# dc-motor.net
KiCad netlist of a schematic drawn in EAGLE
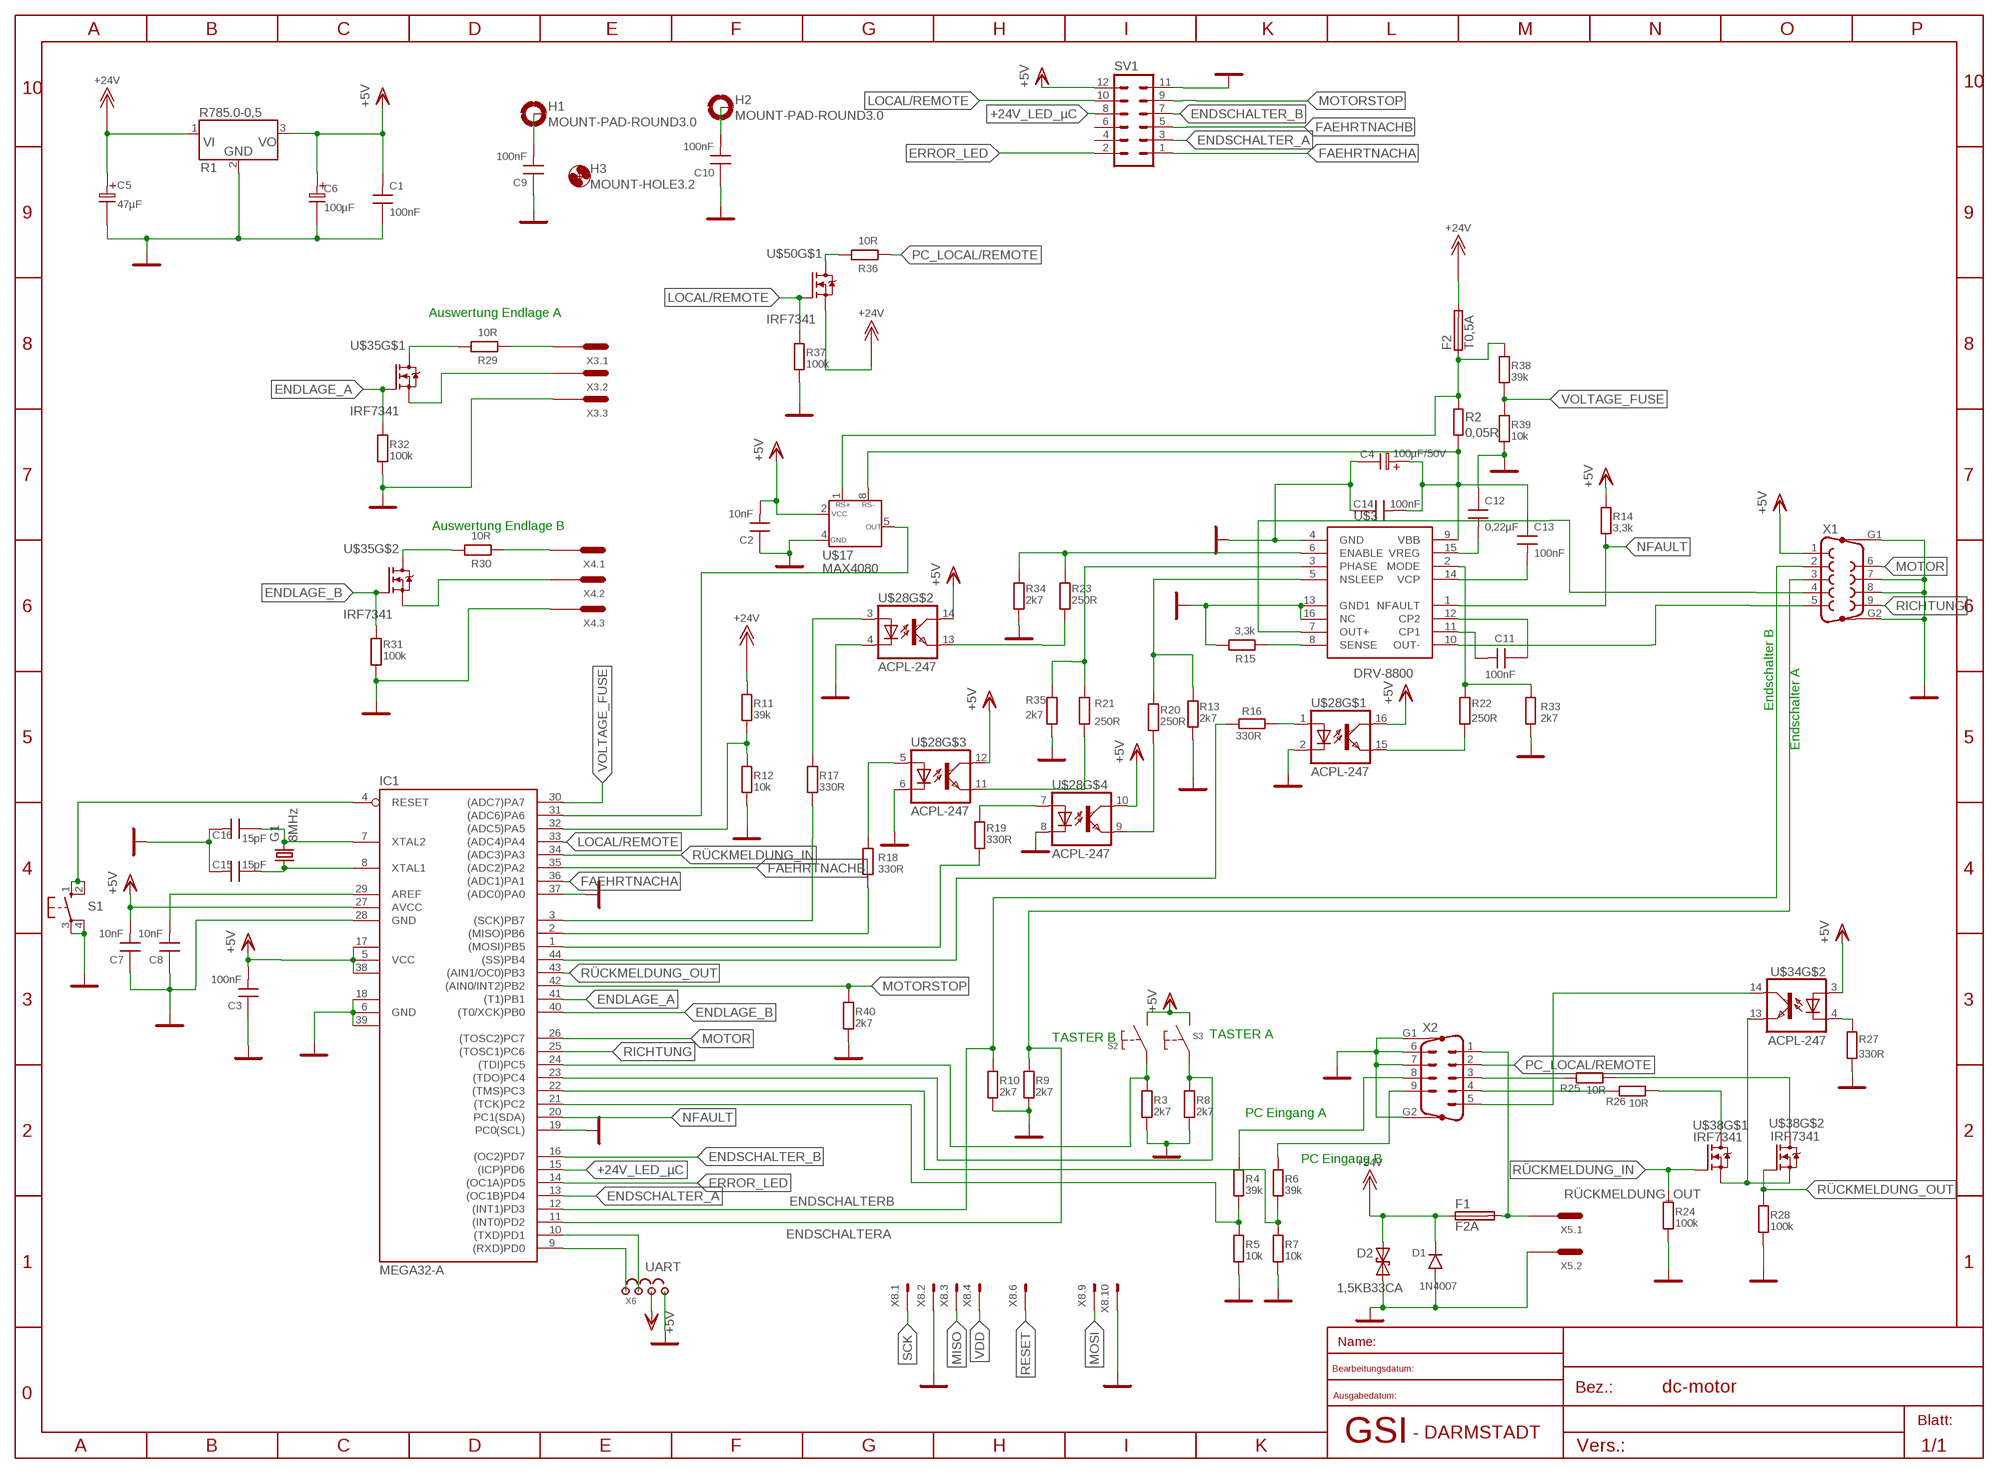
[diagram p0: schematic, sheet 1]

(export (version "E")
  (design (tool "Eeschema 10.0.6"))
  (components
    (comp (ref "C1")
      (value "100nF")
      (footprint "eagle-import:0805")
      (libsource (lib "eagle-import") (part "C-BELAB0805"))
    )
    (comp (ref "C2")
      (value "10nF")
      (footprint "eagle-import:0805")
      (libsource (lib "eagle-import") (part "C-BELAB0805"))
    )
    (comp (ref "C3")
      (value "100nF")
      (footprint "eagle-import:0805")
      (libsource (lib "eagle-import") (part "C-BELAB0805"))
    )
    (comp (ref "C4")
      (value "100µF/50V")
      (footprint "eagle-import:E5-13")
      (libsource (lib "eagle-import") (part "ELK_STEHEND_5_13"))
    )
    (comp (ref "C5")
      (value "47µF")
      (footprint "eagle-import:E5-13")
      (libsource (lib "eagle-import") (part "ELK_STEHEND_5_13"))
    )
    (comp (ref "C6")
      (value "100µF")
      (footprint "eagle-import:E5-13")
      (libsource (lib "eagle-import") (part "ELK_STEHEND_5_13"))
    )
    (comp (ref "C7")
      (value "10nF")
      (footprint "eagle-import:0805")
      (libsource (lib "eagle-import") (part "C-BELAB0805"))
    )
    (comp (ref "C8")
      (value "10nF")
      (footprint "eagle-import:0805")
      (libsource (lib "eagle-import") (part "C-BELAB0805"))
    )
    (comp (ref "C9")
      (value "100nF")
      (footprint "eagle-import:0805")
      (libsource (lib "eagle-import") (part "C-BELAB0805"))
    )
    (comp (ref "C10")
      (value "100nF")
      (footprint "eagle-import:0805")
      (libsource (lib "eagle-import") (part "C-BELAB0805"))
    )
    (comp (ref "C11")
      (value "100nF")
      (footprint "eagle-import:0805")
      (libsource (lib "eagle-import") (part "C-BELAB0805"))
    )
    (comp (ref "C12")
      (value "0,22µF")
      (footprint "eagle-import:0805")
      (libsource (lib "eagle-import") (part "C-BELAB0805"))
    )
    (comp (ref "C13")
      (value "100nF")
      (footprint "eagle-import:0805")
      (libsource (lib "eagle-import") (part "C-BELAB0805"))
    )
    (comp (ref "C14")
      (value "100nF")
      (footprint "eagle-import:0805")
      (libsource (lib "eagle-import") (part "C-BELAB0805"))
    )
    (comp (ref "C15")
      (value "15pF")
      (footprint "eagle-import:0805")
      (libsource (lib "eagle-import") (part "C-BELAB0805"))
    )
    (comp (ref "C16")
      (value "15pF")
      (footprint "eagle-import:0805")
      (libsource (lib "eagle-import") (part "C-BELAB0805"))
    )
    (comp (ref "D1")
      (value "1N4007")
      (footprint "eagle-import:RM10DR1")
      (libsource (lib "eagle-import") (part "1N4007"))
    )
    (comp (ref "D2")
      (value "1,5KB33CA")
      (footprint "eagle-import:CB417-15")
      (libsource (lib "eagle-import") (part "P6KEXXC"))
    )
    (comp (ref "F1")
      (value "F2A")
      (footprint "eagle-import:F457")
      (libsource (lib "eagle-import") (part "F457"))
    )
    (comp (ref "F2")
      (value "T0,5A")
      (footprint "eagle-import:F457")
      (libsource (lib "eagle-import") (part "F457"))
    )
    (comp (ref "G1")
      (value "8MHz")
      (footprint "eagle-import:HC18U-V")
      (libsource (lib "eagle-import") (part "CRYTALHC18U-V"))
    )
    (comp (ref "H1")
      (value "MOUNT-PAD-ROUND3.0")
      (footprint "eagle-import:3,0-PAD")
      (libsource (lib "eagle-import") (part "MOUNT-PAD-ROUND3.0"))
    )
    (comp (ref "H2")
      (value "MOUNT-PAD-ROUND3.0")
      (footprint "eagle-import:3,0-PAD")
      (libsource (lib "eagle-import") (part "MOUNT-PAD-ROUND3.0"))
    )
    (comp (ref "H3")
      (value "MOUNT-HOLE3.2")
      (footprint "eagle-import:3,2")
      (libsource (lib "eagle-import") (part "MOUNT-HOLE3.2"))
    )
    (comp (ref "IC1")
      (value "MEGA32-A")
      (footprint "eagle-import:TQFP44")
      (fields
        (field (name "MPN") "ATMEGA32-16AU")
        (field (name "MPN_1") "ATMEGA32-16AU")
        (field (name "OC_FARNELL") "9171274")
        (field (name "OC_NEWARK") "69K6677")
      )
      (libsource (lib "eagle-import") (part "MEGA32-A"))
    )
    (comp (ref "R1")
      (value "R785.0-0,5")
      (footprint "eagle-import:SIP3")
      (libsource (lib "eagle-import") (part "R-785.0-0.5"))
    )
    (comp (ref "R2")
      (value "0,05R")
      (footprint "eagle-import:SMS-0")
      (libsource (lib "eagle-import") (part "SMS-0"))
    )
    (comp (ref "R3")
      (value "2k7")
      (footprint "eagle-import:0805")
      (libsource (lib "eagle-import") (part "0805"))
    )
    (comp (ref "R4")
      (value "39k")
      (footprint "eagle-import:0805")
      (libsource (lib "eagle-import") (part "0805"))
    )
    (comp (ref "R5")
      (value "10k")
      (footprint "eagle-import:0805")
      (libsource (lib "eagle-import") (part "0805"))
    )
    (comp (ref "R6")
      (value "39k")
      (footprint "eagle-import:0805")
      (libsource (lib "eagle-import") (part "0805"))
    )
    (comp (ref "R7")
      (value "10k")
      (footprint "eagle-import:0805")
      (libsource (lib "eagle-import") (part "0805"))
    )
    (comp (ref "R8")
      (value "2k7")
      (footprint "eagle-import:0805")
      (libsource (lib "eagle-import") (part "0805"))
    )
    (comp (ref "R9")
      (value "2k7")
      (footprint "eagle-import:0805")
      (libsource (lib "eagle-import") (part "0805"))
    )
    (comp (ref "R10")
      (value "2k7")
      (footprint "eagle-import:0805")
      (libsource (lib "eagle-import") (part "0805"))
    )
    (comp (ref "R11")
      (value "39k")
      (footprint "eagle-import:0805")
      (libsource (lib "eagle-import") (part "0805"))
    )
    (comp (ref "R12")
      (value "10k")
      (footprint "eagle-import:0805")
      (libsource (lib "eagle-import") (part "0805"))
    )
    (comp (ref "R13")
      (value "2k7")
      (footprint "eagle-import:0805")
      (libsource (lib "eagle-import") (part "0805"))
    )
    (comp (ref "R14")
      (value "3,3k")
      (footprint "eagle-import:0805")
      (libsource (lib "eagle-import") (part "0805"))
    )
    (comp (ref "R15")
      (value "3,3k")
      (footprint "eagle-import:0805")
      (libsource (lib "eagle-import") (part "0805"))
    )
    (comp (ref "R16")
      (value "330R")
      (footprint "eagle-import:0805")
      (libsource (lib "eagle-import") (part "0805"))
    )
    (comp (ref "R17")
      (value "330R")
      (footprint "eagle-import:0805")
      (libsource (lib "eagle-import") (part "0805"))
    )
    (comp (ref "R18")
      (value "330R")
      (footprint "eagle-import:0805")
      (libsource (lib "eagle-import") (part "0805"))
    )
    (comp (ref "R19")
      (value "330R")
      (footprint "eagle-import:0805")
      (libsource (lib "eagle-import") (part "0805"))
    )
    (comp (ref "R20")
      (value "250R")
      (footprint "eagle-import:0805")
      (libsource (lib "eagle-import") (part "0805"))
    )
    (comp (ref "R21")
      (value "250R")
      (footprint "eagle-import:0805")
      (libsource (lib "eagle-import") (part "0805"))
    )
    (comp (ref "R22")
      (value "250R")
      (footprint "eagle-import:0805")
      (libsource (lib "eagle-import") (part "0805"))
    )
    (comp (ref "R23")
      (value "250R")
      (footprint "eagle-import:0805")
      (libsource (lib "eagle-import") (part "0805"))
    )
    (comp (ref "R24")
      (value "100k")
      (footprint "eagle-import:0805")
      (libsource (lib "eagle-import") (part "0805"))
    )
    (comp (ref "R25")
      (value "10R")
      (footprint "eagle-import:0805")
      (libsource (lib "eagle-import") (part "0805"))
    )
    (comp (ref "R26")
      (value "10R")
      (footprint "eagle-import:0805")
      (libsource (lib "eagle-import") (part "0805"))
    )
    (comp (ref "R27")
      (value "330R")
      (footprint "eagle-import:0805")
      (libsource (lib "eagle-import") (part "0805"))
    )
    (comp (ref "R28")
      (value "100k")
      (footprint "eagle-import:0805")
      (libsource (lib "eagle-import") (part "0805"))
    )
    (comp (ref "R29")
      (value "10R")
      (footprint "eagle-import:0805")
      (libsource (lib "eagle-import") (part "0805"))
    )
    (comp (ref "R30")
      (value "10R")
      (footprint "eagle-import:0805")
      (libsource (lib "eagle-import") (part "0805"))
    )
    (comp (ref "R31")
      (value "100k")
      (footprint "eagle-import:0805")
      (libsource (lib "eagle-import") (part "0805"))
    )
    (comp (ref "R32")
      (value "100k")
      (footprint "eagle-import:0805")
      (libsource (lib "eagle-import") (part "0805"))
    )
    (comp (ref "R33")
      (value "2k7")
      (footprint "eagle-import:0805")
      (libsource (lib "eagle-import") (part "0805"))
    )
    (comp (ref "R34")
      (value "2k7")
      (footprint "eagle-import:0805")
      (libsource (lib "eagle-import") (part "0805"))
    )
    (comp (ref "R35")
      (value "2k7")
      (footprint "eagle-import:0805")
      (libsource (lib "eagle-import") (part "0805"))
    )
    (comp (ref "R36")
      (value "10R")
      (footprint "eagle-import:0805")
      (libsource (lib "eagle-import") (part "0805"))
    )
    (comp (ref "R37")
      (value "100k")
      (footprint "eagle-import:0805")
      (libsource (lib "eagle-import") (part "0805"))
    )
    (comp (ref "R38")
      (value "39k")
      (footprint "eagle-import:0805")
      (libsource (lib "eagle-import") (part "0805"))
    )
    (comp (ref "R39")
      (value "10k")
      (footprint "eagle-import:0805")
      (libsource (lib "eagle-import") (part "0805"))
    )
    (comp (ref "R40")
      (value "2k7")
      (footprint "eagle-import:0805")
      (libsource (lib "eagle-import") (part "0805"))
    )
    (comp (ref "S1")
      (value "10-XX")
      (footprint "eagle-import:B3F-10XX")
      (libsource (lib "eagle-import") (part "10-XX"))
    )
    (comp (ref "S2")
      (value "DRUCKTASTER_ABGW")
      (footprint "eagle-import:1_POL_ABGW")
      (libsource (lib "eagle-import") (part "DRUCKTASTER_ABGW"))
    )
    (comp (ref "S3")
      (value "DRUCKTASTER_ABGW")
      (footprint "eagle-import:1_POL_ABGW")
      (libsource (lib "eagle-import") (part "DRUCKTASTER_ABGW"))
    )
    (comp (ref "SV1")
      (value "MA06-2")
      (footprint "eagle-import:MA06-2")
      (libsource (lib "eagle-import") (part "MA06-2"))
    )
    (comp (ref "U$3")
      (value "DRV-8800")
      (footprint "eagle-import:TSSOP16")
      (libsource (lib "eagle-import") (part "DRV-8800"))
    )
    (comp (ref "U$17")
      (value "MAX4080")
      (footprint "eagle-import:MAX4080")
      (libsource (lib "eagle-import") (part "MAX4080"))
    )
    (comp (ref "U$28")
      (value "ACPL-247")
      (footprint "eagle-import:SOIC16")
      (libsource (lib "eagle-import") (part "ACPL-247"))
    )
    (comp (ref "U$34")
      (value "ACPL-247")
      (footprint "eagle-import:SOIC16")
      (libsource (lib "eagle-import") (part "ACPL-247"))
    )
    (comp (ref "U$35")
      (value "IRF7341")
      (footprint "eagle-import:SO08-IRF")
      (libsource (lib "eagle-import") (part "IRF7341"))
    )
    (comp (ref "U$38")
      (value "IRF7341")
      (footprint "eagle-import:SO08-IRF")
      (libsource (lib "eagle-import") (part "IRF7341"))
    )
    (comp (ref "U$50")
      (value "IRF7341")
      (footprint "eagle-import:SO08-IRF")
      (libsource (lib "eagle-import") (part "IRF7341"))
    )
    (comp (ref "X1")
      (value "F09HP")
      (footprint "eagle-import:F09HP")
      (libsource (lib "eagle-import") (part "F09HP"))
    )
    (comp (ref "X2")
      (value "M09HP")
      (footprint "eagle-import:M09HP")
      (libsource (lib "eagle-import") (part "M09HP"))
    )
    (comp (ref "X3")
      (value "RIA_3POL")
      (footprint "eagle-import:RIA_3POL")
      (libsource (lib "eagle-import") (part "RIA_3POL"))
    )
    (comp (ref "X4")
      (value "RIA_3POL")
      (footprint "eagle-import:RIA_3POL")
      (libsource (lib "eagle-import") (part "RIA_3POL"))
    )
    (comp (ref "X5")
      (value "RIA_2POL")
      (footprint "eagle-import:RIA_2POL")
      (libsource (lib "eagle-import") (part "RIA_2POL"))
    )
    (comp (ref "X6")
      (value "JUMP1-4")
      (footprint "eagle-import:JUMP1-4")
      (libsource (lib "eagle-import") (part "JUMP1-4"))
    )
    (comp (ref "X8")
      (value "PFVERB10")
      (footprint "eagle-import:PFVERB10")
      (libsource (lib "eagle-import") (part "PFVERB10"))
    )
  )
  (nets
    (net (code "1") (name "+24V") (class "Default")
      (node (ref "C5") (pin "+") (pinfunction "+_+") (pintype "passive"))
      (node (ref "D1") (pin "K") (pinfunction "K_K") (pintype "passive"))
      (node (ref "D2") (pin "C") (pinfunction "2_C") (pintype "passive"))
      (node (ref "F1") (pin "1") (pinfunction "1_1") (pintype "passive"))
      (node (ref "F2") (pin "2") (pinfunction "2_2") (pintype "passive"))
      (node (ref "R1") (pin "1") (pinfunction "1_1") (pintype "input"))
      (node (ref "R11") (pin "2") (pinfunction "2_2") (pintype "passive"))
      (node (ref "U$50") (pin "1") (pinfunction "N-S1_1") (pintype "passive"))
    )
    (net (code "2") (name "+24V_LED_µC") (class "Default")
      (node (ref "IC1") (pin "15") (pinfunction "(ICP)PD6_15") (pintype "bidirectional"))
      (node (ref "SV1") (pin "8") (pinfunction "8_8") (pintype "passive"))
    )
    (net (code "3") (name "/ENDSCHALTERA") (class "Default")
      (node (ref "IC1") (pin "11") (pinfunction "(INT0)PD2_11") (pintype "bidirectional"))
      (node (ref "R9") (pin "2") (pinfunction "2_2") (pintype "passive"))
      (node (ref "X1") (pin "3") (pinfunction "3_3") (pintype "passive"))
    )
    (net (code "4") (name "/ENDSCHALTERB") (class "Default")
      (node (ref "IC1") (pin "12") (pinfunction "(INT1)PD3_12") (pintype "bidirectional"))
      (node (ref "R10") (pin "2") (pinfunction "2_2") (pintype "passive"))
      (node (ref "X1") (pin "2") (pinfunction "2_2") (pintype "passive"))
    )
    (net (code "5") (name "ENDLAGE_A") (class "Default")
      (node (ref "IC1") (pin "41") (pinfunction "(T1)PB1_41") (pintype "bidirectional"))
      (node (ref "R32") (pin "1") (pinfunction "1_1") (pintype "passive"))
      (node (ref "U$35") (pin "2") (pinfunction "N-G1_2") (pintype "passive"))
    )
    (net (code "6") (name "ENDLAGE_B") (class "Default")
      (node (ref "IC1") (pin "40") (pinfunction "(T0/XCK)PB0_40") (pintype "bidirectional"))
      (node (ref "R31") (pin "1") (pinfunction "1_1") (pintype "passive"))
      (node (ref "U$35") (pin "4") (pinfunction "N-G1_4") (pintype "passive"))
    )
    (net (code "7") (name "ENDSCHALTER_A") (class "Default")
      (node (ref "IC1") (pin "13") (pinfunction "(OC1B)PD4_13") (pintype "bidirectional"))
      (node (ref "SV1") (pin "3") (pinfunction "3_3") (pintype "passive"))
    )
    (net (code "8") (name "ENDSCHALTER_B") (class "Default")
      (node (ref "IC1") (pin "16") (pinfunction "(OC2)PD7_16") (pintype "bidirectional"))
      (node (ref "SV1") (pin "7") (pinfunction "7_7") (pintype "passive"))
    )
    (net (code "9") (name "ERROR_LED") (class "Default")
      (node (ref "IC1") (pin "14") (pinfunction "(OC1A)PD5_14") (pintype "bidirectional"))
      (node (ref "SV1") (pin "2") (pinfunction "2_2") (pintype "passive"))
    )
    (net (code "10") (name "FAEHRTNACHA") (class "Default")
      (node (ref "IC1") (pin "36") (pinfunction "(ADC1)PA1_36") (pintype "bidirectional"))
      (node (ref "SV1") (pin "1") (pinfunction "1_1") (pintype "passive"))
    )
    (net (code "11") (name "FAEHRTNACHB") (class "Default")
      (node (ref "IC1") (pin "35") (pinfunction "(ADC2)PA2_35") (pintype "bidirectional"))
      (node (ref "SV1") (pin "5") (pinfunction "5_5") (pintype "passive"))
    )
    (net (code "12") (name "GND") (class "Default")
      (node (ref "C1") (pin "1") (pinfunction "1_1") (pintype "passive"))
      (node (ref "C10") (pin "1") (pinfunction "1_1") (pintype "passive"))
      (node (ref "C12") (pin "1") (pinfunction "1_1") (pintype "passive"))
      (node (ref "C14") (pin "1") (pinfunction "1_1") (pintype "passive"))
      (node (ref "C15") (pin "2") (pinfunction "2_2") (pintype "passive"))
      (node (ref "C16") (pin "2") (pinfunction "2_2") (pintype "passive"))
      (node (ref "C2") (pin "1") (pinfunction "1_1") (pintype "passive"))
      (node (ref "C3") (pin "1") (pinfunction "1_1") (pintype "passive"))
      (node (ref "C4") (pin "-") (pinfunction "-_-") (pintype "passive"))
      (node (ref "C5") (pin "-") (pinfunction "-_-") (pintype "passive"))
      (node (ref "C6") (pin "-") (pinfunction "-_-") (pintype "passive"))
      (node (ref "C7") (pin "1") (pinfunction "1_1") (pintype "passive"))
      (node (ref "C8") (pin "1") (pinfunction "1_1") (pintype "passive"))
      (node (ref "C9") (pin "1") (pinfunction "1_1") (pintype "passive"))
      (node (ref "D1") (pin "A") (pinfunction "A_A") (pintype "passive"))
      (node (ref "D2") (pin "A") (pinfunction "1_A") (pintype "passive"))
      (node (ref "IC1") (pin "18") (pinfunction "GND1_18") (pintype "power_in"))
      (node (ref "IC1") (pin "19") (pinfunction "PC0(SCL)_19") (pintype "bidirectional"))
      (node (ref "IC1") (pin "28") (pinfunction "GND_28") (pintype "power_in"))
      (node (ref "IC1") (pin "37") (pinfunction "(ADC0)PA0_37") (pintype "bidirectional"))
      (node (ref "IC1") (pin "39") (pinfunction "GND2_39") (pintype "power_in"))
      (node (ref "IC1") (pin "6") (pinfunction "GND_6") (pintype "power_in"))
      (node (ref "R1") (pin "2") (pinfunction "2_2") (pintype "power_in"))
      (node (ref "R10") (pin "1") (pinfunction "1_1") (pintype "passive"))
      (node (ref "R12") (pin "1") (pinfunction "1_1") (pintype "passive"))
      (node (ref "R13") (pin "1") (pinfunction "1_1") (pintype "passive"))
      (node (ref "R15") (pin "2") (pinfunction "2_2") (pintype "passive"))
      (node (ref "R24") (pin "2") (pinfunction "2_2") (pintype "passive"))
      (node (ref "R27") (pin "1") (pinfunction "1_1") (pintype "passive"))
      (node (ref "R28") (pin "2") (pinfunction "2_2") (pintype "passive"))
      (node (ref "R3") (pin "1") (pinfunction "1_1") (pintype "passive"))
      (node (ref "R31") (pin "2") (pinfunction "2_2") (pintype "passive"))
      (node (ref "R32") (pin "2") (pinfunction "2_2") (pintype "passive"))
      (node (ref "R33") (pin "1") (pinfunction "1_1") (pintype "passive"))
      (node (ref "R34") (pin "1") (pinfunction "1_1") (pintype "passive"))
      (node (ref "R35") (pin "1") (pinfunction "1_1") (pintype "passive"))
      (node (ref "R37") (pin "2") (pinfunction "2_2") (pintype "passive"))
      (node (ref "R39") (pin "1") (pinfunction "1_1") (pintype "passive"))
      (node (ref "R40") (pin "1") (pinfunction "1_1") (pintype "passive"))
      (node (ref "R5") (pin "1") (pinfunction "1_1") (pintype "passive"))
      (node (ref "R7") (pin "1") (pinfunction "1_1") (pintype "passive"))
      (node (ref "R8") (pin "1") (pinfunction "1_1") (pintype "passive"))
      (node (ref "R9") (pin "1") (pinfunction "1_1") (pintype "passive"))
      (node (ref "S1") (pin "3") (pinfunction "P_3") (pintype "passive"))
      (node (ref "S1") (pin "4") (pinfunction "P1_4") (pintype "passive"))
      (node (ref "SV1") (pin "11") (pinfunction "11_11") (pintype "passive"))
      (node (ref "U$17") (pin "4") (pinfunction "GND_4") (pintype "power_in"))
      (node (ref "U$28") (pin "2") (pinfunction "C_2") (pintype "passive"))
      (node (ref "U$28") (pin "4") (pinfunction "C_4") (pintype "passive"))
      (node (ref "U$28") (pin "6") (pinfunction "C_6") (pintype "passive"))
      (node (ref "U$28") (pin "8") (pinfunction "C_8") (pintype "passive"))
      (node (ref "U$3") (pin "13") (pinfunction "GND1_13") (pintype "bidirectional"))
      (node (ref "U$3") (pin "16") (pinfunction "NC_16") (pintype "bidirectional"))
      (node (ref "U$3") (pin "4") (pinfunction "GND_4") (pintype "bidirectional"))
      (node (ref "X1") (pin "7") (pinfunction "7_7") (pintype "passive"))
      (node (ref "X1") (pin "8") (pinfunction "8_8") (pintype "passive"))
      (node (ref "X1") (pin "G1") (pinfunction "G1_G1") (pintype "passive"))
      (node (ref "X1") (pin "G2") (pinfunction "G2_G2") (pintype "passive"))
      (node (ref "X2") (pin "6") (pinfunction "6_6") (pintype "passive"))
      (node (ref "X2") (pin "7") (pinfunction "7_7") (pintype "passive"))
      (node (ref "X2") (pin "G1") (pinfunction "G1_G1") (pintype "passive"))
      (node (ref "X2") (pin "G2") (pinfunction "G2_G2") (pintype "passive"))
      (node (ref "X3") (pin "P$3") (pinfunction "STIFT_P$3") (pintype "passive"))
      (node (ref "X4") (pin "P$3") (pinfunction "STIFT_P$3") (pintype "passive"))
      (node (ref "X5") (pin "P$2") (pinfunction "STIFT_P$2") (pintype "passive"))
      (node (ref "X6") (pin "4") (pinfunction "4_4") (pintype "passive"))
      (node (ref "X8") (pin "10") (pinfunction "1_10") (pintype "passive"))
      (node (ref "X8") (pin "2") (pinfunction "1_2") (pintype "passive"))
    )
    (net (code "13") (name "LOCAL{slash}REMOTE") (class "Default")
      (node (ref "IC1") (pin "33") (pinfunction "(ADC4)PA4_33") (pintype "bidirectional"))
      (node (ref "R37") (pin "1") (pinfunction "1_1") (pintype "passive"))
      (node (ref "SV1") (pin "10") (pinfunction "10_10") (pintype "passive"))
      (node (ref "U$50") (pin "2") (pinfunction "N-G1_2") (pintype "passive"))
    )
    (net (code "14") (name "MISO") (class "Default")
      (node (ref "IC1") (pin "2") (pinfunction "(MISO)PB6_2") (pintype "bidirectional"))
      (node (ref "R18") (pin "2") (pinfunction "2_2") (pintype "passive"))
      (node (ref "X8") (pin "3") (pinfunction "1_3") (pintype "passive"))
    )
    (net (code "15") (name "MOSI") (class "Default")
      (node (ref "IC1") (pin "1") (pinfunction "(MOSI)PB5_1") (pintype "bidirectional"))
      (node (ref "R19") (pin "1") (pinfunction "1_1") (pintype "passive"))
      (node (ref "X8") (pin "9") (pinfunction "1_9") (pintype "passive"))
    )
    (net (code "16") (name "MOTOR") (class "Default")
      (node (ref "IC1") (pin "26") (pinfunction "(TOSC2)PC7_26") (pintype "bidirectional"))
      (node (ref "X1") (pin "6") (pinfunction "6_6") (pintype "passive"))
    )
    (net (code "17") (name "MOTORSTOP") (class "Default")
      (node (ref "IC1") (pin "42") (pinfunction "(AIN0/INT2)PB2_42") (pintype "bidirectional"))
      (node (ref "R40") (pin "2") (pinfunction "2_2") (pintype "passive"))
      (node (ref "SV1") (pin "9") (pinfunction "9_9") (pintype "passive"))
    )
    (net (code "18") (name "NFAULT") (class "Default")
      (node (ref "IC1") (pin "20") (pinfunction "PC1(SDA)_20") (pintype "bidirectional"))
      (node (ref "R14") (pin "1") (pinfunction "1_1") (pintype "passive"))
      (node (ref "U$3") (pin "1") (pinfunction "NFAULT_1") (pintype "bidirectional"))
    )
    (net (code "19") (name "Net-(H1-MOUNT)") (class "Default")
      (node (ref "C9") (pin "2") (pinfunction "2_2") (pintype "passive"))
      (node (ref "H1") (pin "B3,0") (pinfunction "MOUNT_B3,0") (pintype "passive"))
    )
    (net (code "20") (name "Net-(H2-MOUNT)") (class "Default")
      (node (ref "C10") (pin "2") (pinfunction "2_2") (pintype "passive"))
      (node (ref "H2") (pin "B3,0") (pinfunction "MOUNT_B3,0") (pintype "passive"))
    )
    (net (code "21") (name "Net-(IC1-(ADC5)PA5)") (class "Default")
      (node (ref "IC1") (pin "32") (pinfunction "(ADC5)PA5_32") (pintype "bidirectional"))
      (node (ref "R11") (pin "1") (pinfunction "1_1") (pintype "passive"))
      (node (ref "R12") (pin "2") (pinfunction "2_2") (pintype "passive"))
    )
    (net (code "22") (name "Net-(IC1-(ADC6)PA6)") (class "Default")
      (node (ref "IC1") (pin "31") (pinfunction "(ADC6)PA6_31") (pintype "bidirectional"))
      (node (ref "U$17") (pin "5") (pinfunction "OUT_5") (pintype "output"))
    )
    (net (code "23") (name "Net-(IC1-(RXD)PD0)") (class "Default")
      (node (ref "IC1") (pin "9") (pinfunction "(RXD)PD0_9") (pintype "bidirectional"))
      (node (ref "X6") (pin "1") (pinfunction "1_1") (pintype "passive"))
    )
    (net (code "24") (name "Net-(IC1-(SS)PB4)") (class "Default")
      (node (ref "IC1") (pin "44") (pinfunction "(SS)PB4_44") (pintype "bidirectional"))
      (node (ref "R16") (pin "1") (pinfunction "1_1") (pintype "passive"))
    )
    (net (code "25") (name "Net-(IC1-(TCK)PC2)") (class "Default")
      (node (ref "IC1") (pin "21") (pinfunction "(TCK)PC2_21") (pintype "bidirectional"))
      (node (ref "R4") (pin "1") (pinfunction "1_1") (pintype "passive"))
      (node (ref "R5") (pin "2") (pinfunction "2_2") (pintype "passive"))
    )
    (net (code "26") (name "Net-(IC1-(TDI)PC5)") (class "Default")
      (node (ref "IC1") (pin "24") (pinfunction "(TDI)PC5_24") (pintype "bidirectional"))
      (node (ref "R3") (pin "2") (pinfunction "2_2") (pintype "passive"))
      (node (ref "S2") (pin "S1") (pinfunction "C_S1") (pintype "passive"))
    )
    (net (code "27") (name "Net-(IC1-(TDO)PC4)") (class "Default")
      (node (ref "IC1") (pin "23") (pinfunction "(TDO)PC4_23") (pintype "bidirectional"))
      (node (ref "R8") (pin "2") (pinfunction "2_2") (pintype "passive"))
      (node (ref "S3") (pin "S1") (pinfunction "C_S1") (pintype "passive"))
    )
    (net (code "28") (name "Net-(IC1-(TMS)PC3)") (class "Default")
      (node (ref "IC1") (pin "22") (pinfunction "(TMS)PC3_22") (pintype "bidirectional"))
      (node (ref "R6") (pin "1") (pinfunction "1_1") (pintype "passive"))
      (node (ref "R7") (pin "2") (pinfunction "2_2") (pintype "passive"))
    )
    (net (code "29") (name "Net-(IC1-(TXD)PD1)") (class "Default")
      (node (ref "IC1") (pin "10") (pinfunction "(TXD)PD1_10") (pintype "bidirectional"))
      (node (ref "X6") (pin "2") (pinfunction "2_2") (pintype "passive"))
    )
    (net (code "30") (name "Net-(IC1-AREF)") (class "Default")
      (node (ref "C8") (pin "2") (pinfunction "2_2") (pintype "passive"))
      (node (ref "IC1") (pin "29") (pinfunction "AREF_29") (pintype "passive"))
    )
    (net (code "31") (name "Net-(IC1-XTAL1)") (class "Default")
      (node (ref "C15") (pin "1") (pinfunction "1_1") (pintype "passive"))
      (node (ref "G1") (pin "1") (pinfunction "1_1") (pintype "passive"))
      (node (ref "IC1") (pin "8") (pinfunction "XTAL1_8") (pintype "bidirectional"))
    )
    (net (code "32") (name "Net-(IC1-XTAL2)") (class "Default")
      (node (ref "C16") (pin "1") (pinfunction "1_1") (pintype "passive"))
      (node (ref "G1") (pin "2") (pinfunction "2_2") (pintype "passive"))
      (node (ref "IC1") (pin "7") (pinfunction "XTAL2_7") (pintype "bidirectional"))
    )
    (net (code "33") (name "Net-(R4-Pad2)") (class "Default")
      (node (ref "R4") (pin "2") (pinfunction "2_2") (pintype "passive"))
      (node (ref "X2") (pin "8") (pinfunction "8_8") (pintype "passive"))
    )
    (net (code "34") (name "Net-(R6-Pad2)") (class "Default")
      (node (ref "R6") (pin "2") (pinfunction "2_2") (pintype "passive"))
      (node (ref "X2") (pin "9") (pinfunction "9_9") (pintype "passive"))
    )
    (net (code "35") (name "Net-(R25-Pad1)") (class "Default")
      (node (ref "R25") (pin "1") (pinfunction "1_1") (pintype "passive"))
      (node (ref "U$38") (pin "5") (pinfunction "D1_5") (pintype "passive"))
      (node (ref "U$38") (pin "6") (pinfunction "D1_6") (pintype "passive"))
    )
    (net (code "36") (name "Net-(R25-Pad2)") (class "Default")
      (node (ref "R25") (pin "2") (pinfunction "2_2") (pintype "passive"))
      (node (ref "X2") (pin "3") (pinfunction "3_3") (pintype "passive"))
    )
    (net (code "37") (name "Net-(R26-Pad1)") (class "Default")
      (node (ref "R26") (pin "1") (pinfunction "1_1") (pintype "passive"))
      (node (ref "U$38") (pin "7") (pinfunction "D1_7") (pintype "passive"))
      (node (ref "U$38") (pin "8") (pinfunction "D1_8") (pintype "passive"))
    )
    (net (code "38") (name "Net-(R26-Pad2)") (class "Default")
      (node (ref "R26") (pin "2") (pinfunction "2_2") (pintype "passive"))
      (node (ref "X2") (pin "4") (pinfunction "4_4") (pintype "passive"))
    )
    (net (code "39") (name "Net-(R29-Pad2)") (class "Default")
      (node (ref "R29") (pin "2") (pinfunction "2_2") (pintype "passive"))
      (node (ref "U$35") (pin "7") (pinfunction "D1_7") (pintype "passive"))
      (node (ref "U$35") (pin "8") (pinfunction "D1_8") (pintype "passive"))
    )
    (net (code "40") (name "Net-(R30-Pad2)") (class "Default")
      (node (ref "R30") (pin "2") (pinfunction "2_2") (pintype "passive"))
      (node (ref "U$35") (pin "5") (pinfunction "D1_5") (pintype "passive"))
      (node (ref "U$35") (pin "6") (pinfunction "D1_6") (pintype "passive"))
    )
    (net (code "41") (name "Net-(R36-Pad2)") (class "Default")
      (node (ref "R36") (pin "2") (pinfunction "2_2") (pintype "passive"))
      (node (ref "U$50") (pin "7") (pinfunction "D1_7") (pintype "passive"))
      (node (ref "U$50") (pin "8") (pinfunction "D1_8") (pintype "passive"))
    )
    (net (code "42") (name "Net-(U$3-CP1)") (class "Default")
      (node (ref "C11") (pin "2") (pinfunction "2_2") (pintype "passive"))
      (node (ref "U$3") (pin "11") (pinfunction "CP1_11") (pintype "bidirectional"))
    )
    (net (code "43") (name "Net-(U$3-CP2)") (class "Default")
      (node (ref "C11") (pin "1") (pinfunction "1_1") (pintype "passive"))
      (node (ref "U$3") (pin "12") (pinfunction "CP2_12") (pintype "bidirectional"))
    )
    (net (code "44") (name "Net-(U$3-ENABLE)") (class "Default")
      (node (ref "R23") (pin "1") (pinfunction "1_1") (pintype "passive"))
      (node (ref "R34") (pin "2") (pinfunction "2_2") (pintype "passive"))
      (node (ref "U$3") (pin "6") (pinfunction "ENABLE_6") (pintype "bidirectional"))
    )
    (net (code "45") (name "Net-(U$3-MODE)") (class "Default")
      (node (ref "R22") (pin "1") (pinfunction "1_1") (pintype "passive"))
      (node (ref "R33") (pin "2") (pinfunction "2_2") (pintype "passive"))
      (node (ref "U$3") (pin "2") (pinfunction "MODE_2") (pintype "bidirectional"))
    )
    (net (code "46") (name "Net-(U$3-NSLEEP)") (class "Default")
      (node (ref "R13") (pin "2") (pinfunction "2_2") (pintype "passive"))
      (node (ref "R20") (pin "1") (pinfunction "1_1") (pintype "passive"))
      (node (ref "U$3") (pin "5") (pinfunction "NSLEEP_5") (pintype "bidirectional"))
    )
    (net (code "47") (name "Net-(U$3-OUT+)") (class "Default")
      (node (ref "U$3") (pin "7") (pinfunction "OUT+_7") (pintype "bidirectional"))
      (node (ref "X1") (pin "4") (pinfunction "4_4") (pintype "passive"))
    )
    (net (code "48") (name "Net-(U$3-OUT-)") (class "Default")
      (node (ref "U$3") (pin "10") (pinfunction "OUT-_10") (pintype "bidirectional"))
      (node (ref "X1") (pin "5") (pinfunction "5_5") (pintype "passive"))
    )
    (net (code "49") (name "Net-(U$3-PHASE)") (class "Default")
      (node (ref "R21") (pin "1") (pinfunction "1_1") (pintype "passive"))
      (node (ref "R35") (pin "2") (pinfunction "2_2") (pintype "passive"))
      (node (ref "U$3") (pin "3") (pinfunction "PHASE_3") (pintype "bidirectional"))
    )
    (net (code "50") (name "Net-(U$3-SENSE)") (class "Default")
      (node (ref "R15") (pin "1") (pinfunction "1_1") (pintype "passive"))
      (node (ref "U$3") (pin "8") (pinfunction "SENSE_8") (pintype "bidirectional"))
    )
    (net (code "51") (name "Net-(U$3-VCP)") (class "Default")
      (node (ref "C13") (pin "2") (pinfunction "2_2") (pintype "passive"))
      (node (ref "U$3") (pin "14") (pinfunction "VCP_14") (pintype "bidirectional"))
    )
    (net (code "52") (name "Net-(U$3-VREG)") (class "Default")
      (node (ref "C12") (pin "2") (pinfunction "2_2") (pintype "passive"))
      (node (ref "U$3") (pin "15") (pinfunction "VREG_15") (pintype "bidirectional"))
    )
    (net (code "53") (name "Net-(U$17-RS+)") (class "Default")
      (node (ref "F2") (pin "1") (pinfunction "1_1") (pintype "passive"))
      (node (ref "R2") (pin "1") (pinfunction "1_1") (pintype "passive"))
      (node (ref "R38") (pin "2") (pinfunction "2_2") (pintype "passive"))
      (node (ref "U$17") (pin "1") (pinfunction "RS+_1") (pintype "input"))
    )
    (net (code "54") (name "Net-(U$17-RS-)") (class "Default")
      (node (ref "C13") (pin "1") (pinfunction "1_1") (pintype "passive"))
      (node (ref "C14") (pin "2") (pinfunction "2_2") (pintype "passive"))
      (node (ref "C4") (pin "+") (pinfunction "+_+") (pintype "passive"))
      (node (ref "R2") (pin "2") (pinfunction "2_2") (pintype "passive"))
      (node (ref "U$17") (pin "8") (pinfunction "RS-_8") (pintype "input"))
      (node (ref "U$3") (pin "9") (pinfunction "VBB_9") (pintype "bidirectional"))
    )
    (net (code "55") (name "Net-(U$28A-A)") (class "Default")
      (node (ref "R16") (pin "2") (pinfunction "2_2") (pintype "passive"))
      (node (ref "U$28") (pin "1") (pinfunction "A_1") (pintype "passive"))
    )
    (net (code "56") (name "Net-(U$28A-EMIT)") (class "Default")
      (node (ref "R22") (pin "2") (pinfunction "2_2") (pintype "passive"))
      (node (ref "U$28") (pin "15") (pinfunction "EMIT_15") (pintype "passive"))
    )
    (net (code "57") (name "Net-(U$28B-A)") (class "Default")
      (node (ref "R17") (pin "1") (pinfunction "1_1") (pintype "passive"))
      (node (ref "U$28") (pin "3") (pinfunction "A_3") (pintype "passive"))
    )
    (net (code "58") (name "Net-(U$28B-EMIT)") (class "Default")
      (node (ref "R23") (pin "2") (pinfunction "2_2") (pintype "passive"))
      (node (ref "U$28") (pin "13") (pinfunction "EMIT_13") (pintype "passive"))
    )
    (net (code "59") (name "Net-(U$28C-A)") (class "Default")
      (node (ref "R18") (pin "1") (pinfunction "1_1") (pintype "passive"))
      (node (ref "U$28") (pin "5") (pinfunction "A_5") (pintype "passive"))
    )
    (net (code "60") (name "Net-(U$28C-EMIT)") (class "Default")
      (node (ref "R21") (pin "2") (pinfunction "2_2") (pintype "passive"))
      (node (ref "U$28") (pin "11") (pinfunction "EMIT_11") (pintype "passive"))
    )
    (net (code "61") (name "Net-(U$28D-A)") (class "Default")
      (node (ref "R19") (pin "2") (pinfunction "2_2") (pintype "passive"))
      (node (ref "U$28") (pin "7") (pinfunction "A_7") (pintype "passive"))
    )
    (net (code "62") (name "Net-(U$28D-EMIT)") (class "Default")
      (node (ref "R20") (pin "2") (pinfunction "2_2") (pintype "passive"))
      (node (ref "U$28") (pin "9") (pinfunction "EMIT_9") (pintype "passive"))
    )
    (net (code "63") (name "Net-(U$34B-C)") (class "Default")
      (node (ref "R27") (pin "2") (pinfunction "2_2") (pintype "passive"))
      (node (ref "U$34") (pin "4") (pinfunction "C_4") (pintype "passive"))
    )
    (net (code "64") (name "Net-(U$34B-COL)") (class "Default")
      (node (ref "U$34") (pin "14") (pinfunction "COL_14") (pintype "passive"))
      (node (ref "X2") (pin "5") (pinfunction "5_5") (pintype "passive"))
    )
    (net (code "65") (name "Net-(U$34B-EMIT)") (class "Default")
      (node (ref "U$34") (pin "13") (pinfunction "EMIT_13") (pintype "passive"))
      (node (ref "U$38") (pin "1") (pinfunction "N-S1_1") (pintype "passive"))
      (node (ref "U$38") (pin "3") (pinfunction "N-S1_3") (pintype "passive"))
    )
    (net (code "66") (name "Net-(U$35A-N-S1)") (class "Default")
      (node (ref "U$35") (pin "1") (pinfunction "N-S1_1") (pintype "passive"))
      (node (ref "X3") (pin "P$2") (pinfunction "STIFT_P$2") (pintype "passive"))
    )
    (net (code "67") (name "Net-(U$35B-N-S1)") (class "Default")
      (node (ref "U$35") (pin "3") (pinfunction "N-S1_3") (pintype "passive"))
      (node (ref "X4") (pin "P$2") (pinfunction "STIFT_P$2") (pintype "passive"))
    )
    (net (code "68") (name "Net-(X3A-STIFT)") (class "Default")
      (node (ref "R29") (pin "1") (pinfunction "1_1") (pintype "passive"))
      (node (ref "X3") (pin "P$1") (pinfunction "STIFT_P$1") (pintype "passive"))
    )
    (net (code "69") (name "Net-(X4A-STIFT)") (class "Default")
      (node (ref "R30") (pin "1") (pinfunction "1_1") (pintype "passive"))
      (node (ref "X4") (pin "P$1") (pinfunction "STIFT_P$1") (pintype "passive"))
    )
    (net (code "70") (name "Net-(X5A-STIFT)") (class "Default")
      (node (ref "F1") (pin "2") (pinfunction "2_2") (pintype "passive"))
      (node (ref "X2") (pin "1") (pinfunction "1_1") (pintype "passive"))
      (node (ref "X5") (pin "P$1") (pinfunction "STIFT_P$1") (pintype "passive"))
    )
    (net (code "71") (name "PC_LOCAL{slash}REMOTE") (class "Default")
      (node (ref "R36") (pin "1") (pinfunction "1_1") (pintype "passive"))
      (node (ref "X2") (pin "2") (pinfunction "2_2") (pintype "passive"))
    )
    (net (code "72") (name "RESET") (class "Default")
      (node (ref "IC1") (pin "4") (pinfunction "RESET_4") (pintype "input"))
      (node (ref "S1") (pin "1") (pinfunction "S_1") (pintype "passive"))
      (node (ref "S1") (pin "2") (pinfunction "S1_2") (pintype "passive"))
      (node (ref "X8") (pin "6") (pinfunction "1_6") (pintype "passive"))
    )
    (net (code "73") (name "RICHTUNG") (class "Default")
      (node (ref "IC1") (pin "25") (pinfunction "(TOSC1)PC6_25") (pintype "bidirectional"))
      (node (ref "X1") (pin "9") (pinfunction "9_9") (pintype "passive"))
    )
    (net (code "74") (name "RÜCKMELDUNG_IN") (class "Default")
      (node (ref "IC1") (pin "34") (pinfunction "(ADC3)PA3_34") (pintype "bidirectional"))
      (node (ref "R24") (pin "1") (pinfunction "1_1") (pintype "passive"))
      (node (ref "U$38") (pin "2") (pinfunction "N-G1_2") (pintype "passive"))
    )
    (net (code "75") (name "RÜCKMELDUNG_OUT") (class "Default")
      (node (ref "IC1") (pin "43") (pinfunction "(AIN1/OC0)PB3_43") (pintype "bidirectional"))
      (node (ref "R28") (pin "1") (pinfunction "1_1") (pintype "passive"))
      (node (ref "U$38") (pin "4") (pinfunction "N-G1_4") (pintype "passive"))
    )
    (net (code "76") (name "SCK") (class "Default")
      (node (ref "IC1") (pin "3") (pinfunction "(SCK)PB7_3") (pintype "bidirectional"))
      (node (ref "R17") (pin "2") (pinfunction "2_2") (pintype "passive"))
      (node (ref "X8") (pin "1") (pinfunction "1_1") (pintype "passive"))
    )
    (net (code "77") (name "VDD") (class "Default")
      (node (ref "C1") (pin "2") (pinfunction "2_2") (pintype "passive"))
      (node (ref "C2") (pin "2") (pinfunction "2_2") (pintype "passive"))
      (node (ref "C3") (pin "2") (pinfunction "2_2") (pintype "passive"))
      (node (ref "C6") (pin "+") (pinfunction "+_+") (pintype "passive"))
      (node (ref "C7") (pin "2") (pinfunction "2_2") (pintype "passive"))
      (node (ref "IC1") (pin "17") (pinfunction "VCC1_17") (pintype "power_in"))
      (node (ref "IC1") (pin "27") (pinfunction "AVCC_27") (pintype "power_in"))
      (node (ref "IC1") (pin "38") (pinfunction "VCC2_38") (pintype "power_in"))
      (node (ref "IC1") (pin "5") (pinfunction "VCC_5") (pintype "power_in"))
      (node (ref "R1") (pin "3") (pinfunction "3_3") (pintype "output"))
      (node (ref "R14") (pin "2") (pinfunction "2_2") (pintype "passive"))
      (node (ref "S2") (pin "S2") (pinfunction "N0_S2") (pintype "passive"))
      (node (ref "S3") (pin "S2") (pinfunction "N0_S2") (pintype "passive"))
      (node (ref "SV1") (pin "12") (pinfunction "12_12") (pintype "passive"))
      (node (ref "U$17") (pin "2") (pinfunction "VCC_2") (pintype "power_in"))
      (node (ref "U$28") (pin "10") (pinfunction "COL_10") (pintype "passive"))
      (node (ref "U$28") (pin "12") (pinfunction "COL_12") (pintype "passive"))
      (node (ref "U$28") (pin "14") (pinfunction "COL_14") (pintype "passive"))
      (node (ref "U$28") (pin "16") (pinfunction "COL_16") (pintype "passive"))
      (node (ref "U$34") (pin "3") (pinfunction "A_3") (pintype "passive"))
      (node (ref "X1") (pin "1") (pinfunction "1_1") (pintype "passive"))
      (node (ref "X6") (pin "3") (pinfunction "3_3") (pintype "passive"))
      (node (ref "X8") (pin "4") (pinfunction "1_4") (pintype "passive"))
    )
    (net (code "78") (name "VOLTAGE_FUSE") (class "Default")
      (node (ref "IC1") (pin "30") (pinfunction "(ADC7)PA7_30") (pintype "bidirectional"))
      (node (ref "R38") (pin "1") (pinfunction "1_1") (pintype "passive"))
      (node (ref "R39") (pin "2") (pinfunction "2_2") (pintype "passive"))
    )
    (net (code "79") (name "unconnected-(SV1-Pad4)") (class "Default")
      (node (ref "SV1") (pin "4") (pinfunction "4_4") (pintype "passive"))
    )
    (net (code "80") (name "unconnected-(SV1-Pad6)") (class "Default")
      (node (ref "SV1") (pin "6") (pinfunction "6_6") (pintype "passive"))
    )
  )
)
